# BasicGates2.net
KiCad netlist of a schematic drawn in EAGLE
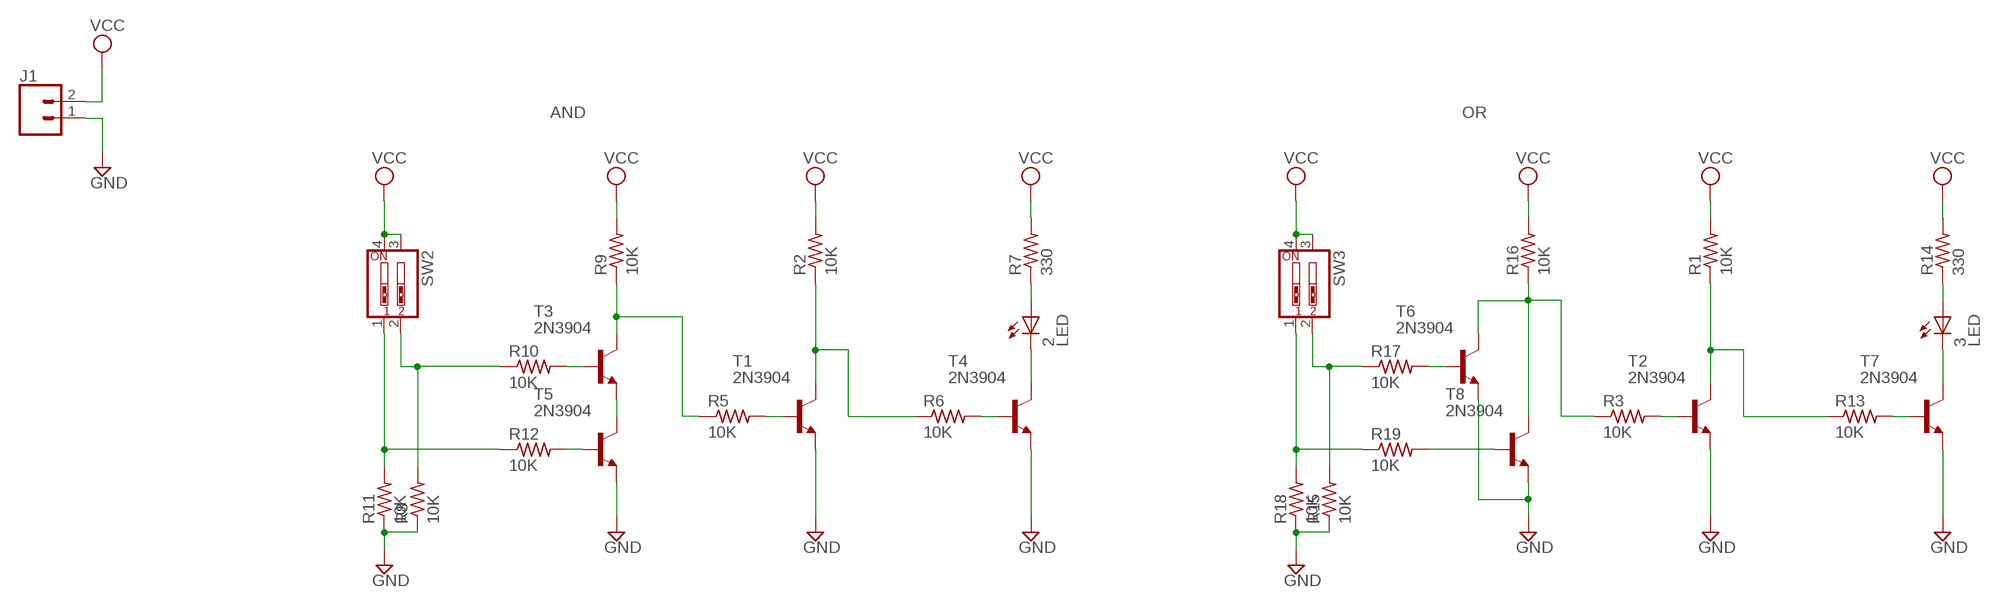
[diagram p0: schematic, sheet 1]

(export (version "E")
  (design (tool "Eeschema 10.0.6"))
  (components
    (comp (ref "2")
      (value "LED")
      (footprint "eagle-import:LED5MM")
      (libsource (lib "eagle-import") (part "LED5MM"))
    )
    (comp (ref "3")
      (value "LED")
      (footprint "eagle-import:LED5MM")
      (libsource (lib "eagle-import") (part "LED5MM"))
    )
    (comp (ref "J1")
      (value "CONN_02")
      (footprint "eagle-import:1X02")
      (libsource (lib "eagle-import") (part "CONN_02"))
    )
    (comp (ref "R1")
      (value "10K")
      (footprint "eagle-import:0309_10")
      (libsource (lib "eagle-import") (part "R-US_0309/10"))
    )
    (comp (ref "R2")
      (value "10K")
      (footprint "eagle-import:0309_10")
      (libsource (lib "eagle-import") (part "R-US_0309/10"))
    )
    (comp (ref "R3")
      (value "10K")
      (footprint "eagle-import:0309_10")
      (libsource (lib "eagle-import") (part "R-US_0309/10"))
    )
    (comp (ref "R5")
      (value "10K")
      (footprint "eagle-import:0309_10")
      (libsource (lib "eagle-import") (part "R-US_0309/10"))
    )
    (comp (ref "R6")
      (value "10K")
      (footprint "eagle-import:0309_10")
      (libsource (lib "eagle-import") (part "R-US_0309/10"))
    )
    (comp (ref "R7")
      (value "330")
      (footprint "eagle-import:0309_10")
      (libsource (lib "eagle-import") (part "R-US_0309/10"))
    )
    (comp (ref "R8")
      (value "10K")
      (footprint "eagle-import:0309_10")
      (libsource (lib "eagle-import") (part "R-US_0309/10"))
    )
    (comp (ref "R9")
      (value "10K")
      (footprint "eagle-import:0309_10")
      (libsource (lib "eagle-import") (part "R-US_0309/10"))
    )
    (comp (ref "R10")
      (value "10K")
      (footprint "eagle-import:0309_10")
      (libsource (lib "eagle-import") (part "R-US_0309/10"))
    )
    (comp (ref "R11")
      (value "10K")
      (footprint "eagle-import:0309_10")
      (libsource (lib "eagle-import") (part "R-US_0309/10"))
    )
    (comp (ref "R12")
      (value "10K")
      (footprint "eagle-import:0309_10")
      (libsource (lib "eagle-import") (part "R-US_0309/10"))
    )
    (comp (ref "R13")
      (value "10K")
      (footprint "eagle-import:0309_10")
      (libsource (lib "eagle-import") (part "R-US_0309/10"))
    )
    (comp (ref "R14")
      (value "330")
      (footprint "eagle-import:0309_10")
      (libsource (lib "eagle-import") (part "R-US_0309/10"))
    )
    (comp (ref "R15")
      (value "10K")
      (footprint "eagle-import:0309_10")
      (libsource (lib "eagle-import") (part "R-US_0309/10"))
    )
    (comp (ref "R16")
      (value "10K")
      (footprint "eagle-import:0309_10")
      (libsource (lib "eagle-import") (part "R-US_0309/10"))
    )
    (comp (ref "R17")
      (value "10K")
      (footprint "eagle-import:0309_10")
      (libsource (lib "eagle-import") (part "R-US_0309/10"))
    )
    (comp (ref "R18")
      (value "10K")
      (footprint "eagle-import:0309_10")
      (libsource (lib "eagle-import") (part "R-US_0309/10"))
    )
    (comp (ref "R19")
      (value "10K")
      (footprint "eagle-import:0309_10")
      (libsource (lib "eagle-import") (part "R-US_0309/10"))
    )
    (comp (ref "SW2")
      (value "SW_DIP-2")
      (footprint "eagle-import:EDG-02")
      (libsource (lib "eagle-import") (part "SW_DIP-2"))
    )
    (comp (ref "SW3")
      (value "SW_DIP-2")
      (footprint "eagle-import:EDG-02")
      (libsource (lib "eagle-import") (part "SW_DIP-2"))
    )
    (comp (ref "T1")
      (value "2N3904")
      (footprint "eagle-import:TO92")
      (libsource (lib "eagle-import") (part "2N3904"))
    )
    (comp (ref "T2")
      (value "2N3904")
      (footprint "eagle-import:TO92")
      (libsource (lib "eagle-import") (part "2N3904"))
    )
    (comp (ref "T3")
      (value "2N3904")
      (footprint "eagle-import:TO92")
      (libsource (lib "eagle-import") (part "2N3904"))
    )
    (comp (ref "T4")
      (value "2N3904")
      (footprint "eagle-import:TO92")
      (libsource (lib "eagle-import") (part "2N3904"))
    )
    (comp (ref "T5")
      (value "2N3904")
      (footprint "eagle-import:TO92")
      (libsource (lib "eagle-import") (part "2N3904"))
    )
    (comp (ref "T6")
      (value "2N3904")
      (footprint "eagle-import:TO92")
      (libsource (lib "eagle-import") (part "2N3904"))
    )
    (comp (ref "T7")
      (value "2N3904")
      (footprint "eagle-import:TO92")
      (libsource (lib "eagle-import") (part "2N3904"))
    )
    (comp (ref "T8")
      (value "2N3904")
      (footprint "eagle-import:TO92")
      (libsource (lib "eagle-import") (part "2N3904"))
    )
  )
  (nets
    (net (code "1") (name "GND") (class "Default")
      (node (ref "J1") (pin "1") (pinfunction "1_1") (pintype "passive"))
      (node (ref "R11") (pin "1") (pinfunction "1_1") (pintype "passive"))
      (node (ref "R15") (pin "1") (pinfunction "1_1") (pintype "passive"))
      (node (ref "R18") (pin "1") (pinfunction "1_1") (pintype "passive"))
      (node (ref "R8") (pin "1") (pinfunction "1_1") (pintype "passive"))
      (node (ref "T1") (pin "3") (pinfunction "E_3") (pintype "passive"))
      (node (ref "T2") (pin "3") (pinfunction "E_3") (pintype "passive"))
      (node (ref "T4") (pin "3") (pinfunction "E_3") (pintype "passive"))
      (node (ref "T5") (pin "3") (pinfunction "E_3") (pintype "passive"))
      (node (ref "T6") (pin "3") (pinfunction "E_3") (pintype "passive"))
      (node (ref "T7") (pin "3") (pinfunction "E_3") (pintype "passive"))
      (node (ref "T8") (pin "3") (pinfunction "E_3") (pintype "passive"))
    )
    (net (code "2") (name "Net-(2-C)") (class "Default")
      (node (ref "2") (pin "K") (pinfunction "C_K") (pintype "passive"))
      (node (ref "T4") (pin "1") (pinfunction "C_1") (pintype "passive"))
    )
    (net (code "3") (name "Net-(2-PadA)") (class "Default")
      (node (ref "2") (pin "A") (pinfunction "A_A") (pintype "passive"))
      (node (ref "R7") (pin "1") (pinfunction "1_1") (pintype "passive"))
    )
    (net (code "4") (name "Net-(3-C)") (class "Default")
      (node (ref "3") (pin "K") (pinfunction "C_K") (pintype "passive"))
      (node (ref "T7") (pin "1") (pinfunction "C_1") (pintype "passive"))
    )
    (net (code "5") (name "Net-(3-PadA)") (class "Default")
      (node (ref "3") (pin "A") (pinfunction "A_A") (pintype "passive"))
      (node (ref "R14") (pin "1") (pinfunction "1_1") (pintype "passive"))
    )
    (net (code "6") (name "Net-(R10-Pad1)") (class "Default")
      (node (ref "R10") (pin "1") (pinfunction "1_1") (pintype "passive"))
      (node (ref "R8") (pin "2") (pinfunction "2_2") (pintype "passive"))
      (node (ref "SW2") (pin "2") (pinfunction "2_2") (pintype "passive"))
    )
    (net (code "7") (name "Net-(R11-Pad2)") (class "Default")
      (node (ref "R11") (pin "2") (pinfunction "2_2") (pintype "passive"))
      (node (ref "R12") (pin "1") (pinfunction "1_1") (pintype "passive"))
      (node (ref "SW2") (pin "1") (pinfunction "1_1") (pintype "passive"))
    )
    (net (code "8") (name "Net-(R15-Pad2)") (class "Default")
      (node (ref "R15") (pin "2") (pinfunction "2_2") (pintype "passive"))
      (node (ref "R17") (pin "1") (pinfunction "1_1") (pintype "passive"))
      (node (ref "SW3") (pin "2") (pinfunction "2_2") (pintype "passive"))
    )
    (net (code "9") (name "Net-(R18-Pad2)") (class "Default")
      (node (ref "R18") (pin "2") (pinfunction "2_2") (pintype "passive"))
      (node (ref "R19") (pin "1") (pinfunction "1_1") (pintype "passive"))
      (node (ref "SW3") (pin "1") (pinfunction "1_1") (pintype "passive"))
    )
    (net (code "10") (name "Net-(T1-B)") (class "Default")
      (node (ref "R5") (pin "2") (pinfunction "2_2") (pintype "passive"))
      (node (ref "T1") (pin "2") (pinfunction "B_2") (pintype "passive"))
    )
    (net (code "11") (name "Net-(T1-C)") (class "Default")
      (node (ref "R2") (pin "1") (pinfunction "1_1") (pintype "passive"))
      (node (ref "R6") (pin "1") (pinfunction "1_1") (pintype "passive"))
      (node (ref "T1") (pin "1") (pinfunction "C_1") (pintype "passive"))
    )
    (net (code "12") (name "Net-(T2-B)") (class "Default")
      (node (ref "R3") (pin "2") (pinfunction "2_2") (pintype "passive"))
      (node (ref "T2") (pin "2") (pinfunction "B_2") (pintype "passive"))
    )
    (net (code "13") (name "Net-(T2-C)") (class "Default")
      (node (ref "R1") (pin "1") (pinfunction "1_1") (pintype "passive"))
      (node (ref "R13") (pin "1") (pinfunction "1_1") (pintype "passive"))
      (node (ref "T2") (pin "1") (pinfunction "C_1") (pintype "passive"))
    )
    (net (code "14") (name "Net-(T3-B)") (class "Default")
      (node (ref "R10") (pin "2") (pinfunction "2_2") (pintype "passive"))
      (node (ref "T3") (pin "2") (pinfunction "B_2") (pintype "passive"))
    )
    (net (code "15") (name "Net-(T3-C)") (class "Default")
      (node (ref "R5") (pin "1") (pinfunction "1_1") (pintype "passive"))
      (node (ref "R9") (pin "1") (pinfunction "1_1") (pintype "passive"))
      (node (ref "T3") (pin "1") (pinfunction "C_1") (pintype "passive"))
    )
    (net (code "16") (name "Net-(T3-E)") (class "Default")
      (node (ref "T3") (pin "3") (pinfunction "E_3") (pintype "passive"))
      (node (ref "T5") (pin "1") (pinfunction "C_1") (pintype "passive"))
    )
    (net (code "17") (name "Net-(T4-B)") (class "Default")
      (node (ref "R6") (pin "2") (pinfunction "2_2") (pintype "passive"))
      (node (ref "T4") (pin "2") (pinfunction "B_2") (pintype "passive"))
    )
    (net (code "18") (name "Net-(T5-B)") (class "Default")
      (node (ref "R12") (pin "2") (pinfunction "2_2") (pintype "passive"))
      (node (ref "T5") (pin "2") (pinfunction "B_2") (pintype "passive"))
    )
    (net (code "19") (name "Net-(T6-B)") (class "Default")
      (node (ref "R17") (pin "2") (pinfunction "2_2") (pintype "passive"))
      (node (ref "T6") (pin "2") (pinfunction "B_2") (pintype "passive"))
    )
    (net (code "20") (name "Net-(T6-C)") (class "Default")
      (node (ref "R16") (pin "1") (pinfunction "1_1") (pintype "passive"))
      (node (ref "R3") (pin "1") (pinfunction "1_1") (pintype "passive"))
      (node (ref "T6") (pin "1") (pinfunction "C_1") (pintype "passive"))
      (node (ref "T8") (pin "1") (pinfunction "C_1") (pintype "passive"))
    )
    (net (code "21") (name "Net-(T7-B)") (class "Default")
      (node (ref "R13") (pin "2") (pinfunction "2_2") (pintype "passive"))
      (node (ref "T7") (pin "2") (pinfunction "B_2") (pintype "passive"))
    )
    (net (code "22") (name "Net-(T8-B)") (class "Default")
      (node (ref "R19") (pin "2") (pinfunction "2_2") (pintype "passive"))
      (node (ref "T8") (pin "2") (pinfunction "B_2") (pintype "passive"))
    )
    (net (code "23") (name "VCC") (class "Default")
      (node (ref "J1") (pin "2") (pinfunction "2_2") (pintype "passive"))
      (node (ref "R1") (pin "2") (pinfunction "2_2") (pintype "passive"))
      (node (ref "R14") (pin "2") (pinfunction "2_2") (pintype "passive"))
      (node (ref "R16") (pin "2") (pinfunction "2_2") (pintype "passive"))
      (node (ref "R2") (pin "2") (pinfunction "2_2") (pintype "passive"))
      (node (ref "R7") (pin "2") (pinfunction "2_2") (pintype "passive"))
      (node (ref "R9") (pin "2") (pinfunction "2_2") (pintype "passive"))
      (node (ref "SW2") (pin "3") (pinfunction "3_3") (pintype "passive"))
      (node (ref "SW2") (pin "4") (pinfunction "4_4") (pintype "passive"))
      (node (ref "SW3") (pin "3") (pinfunction "3_3") (pintype "passive"))
      (node (ref "SW3") (pin "4") (pinfunction "4_4") (pintype "passive"))
    )
  )
)
